# MIDI_Output.net
KiCad netlist of a schematic drawn in EAGLE
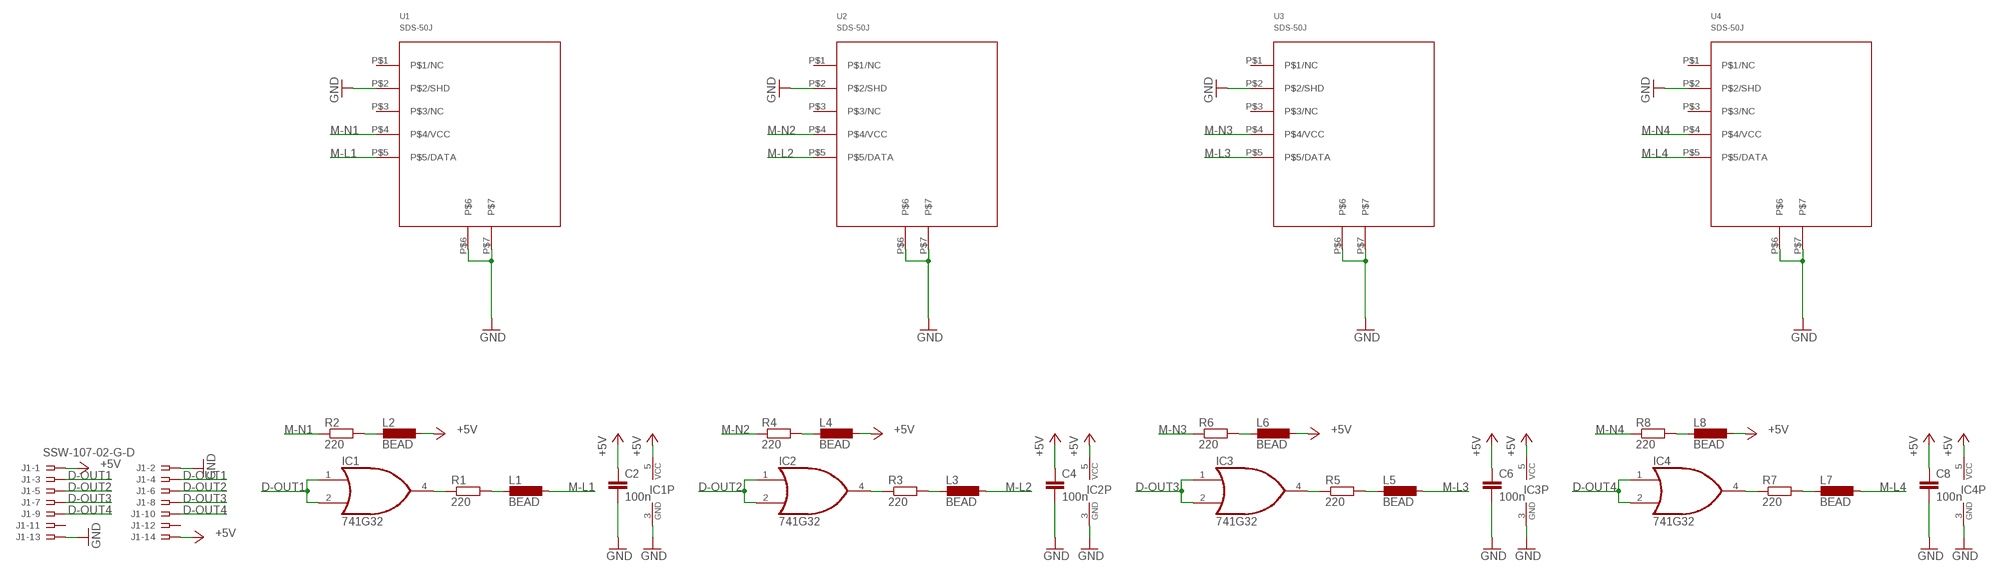
[diagram p0: schematic, sheet 1]

(export (version "E")
  (design (tool "Eeschema 10.0.6"))
  (components
    (comp (ref "C2")
      (value "100n")
      (footprint "eagle-import:C0805")
      (libsource (lib "eagle-import") (part "C-EUC0805"))
    )
    (comp (ref "C4")
      (value "100n")
      (footprint "eagle-import:C0805")
      (libsource (lib "eagle-import") (part "C-EUC0805"))
    )
    (comp (ref "C6")
      (value "100n")
      (footprint "eagle-import:C0805")
      (libsource (lib "eagle-import") (part "C-EUC0805"))
    )
    (comp (ref "C8")
      (value "100n")
      (footprint "eagle-import:C0805")
      (libsource (lib "eagle-import") (part "C-EUC0805"))
    )
    (comp (ref "IC1")
      (value "741G32")
      (footprint "eagle-import:SOT25")
      (fields (field (name "SPICEPREFIX") "J"))
      (libsource (lib "eagle-import") (part "741G32"))
    )
    (comp (ref "IC2")
      (value "741G32")
      (footprint "eagle-import:SOT25")
      (fields (field (name "SPICEPREFIX") "J"))
      (libsource (lib "eagle-import") (part "741G32"))
    )
    (comp (ref "IC3")
      (value "741G32")
      (footprint "eagle-import:SOT25")
      (fields (field (name "SPICEPREFIX") "J"))
      (libsource (lib "eagle-import") (part "741G32"))
    )
    (comp (ref "IC4")
      (value "741G32")
      (footprint "eagle-import:SOT25")
      (fields (field (name "SPICEPREFIX") "J"))
      (libsource (lib "eagle-import") (part "741G32"))
    )
    (comp (ref "J1")
      (value "SSW-107-02-G-D")
      (footprint "eagle-import:SSW-107-02-G-D")
      (fields (field (name "MF") "Samtec Inc."))
      (libsource (lib "eagle-import") (part "SSW-107-02-G-D"))
    )
    (comp (ref "L1")
      (value "BEAD")
      (footprint "eagle-import:L0805")
      (libsource (lib "eagle-import") (part "BEAD"))
    )
    (comp (ref "L2")
      (value "BEAD")
      (footprint "eagle-import:L0805")
      (libsource (lib "eagle-import") (part "BEAD"))
    )
    (comp (ref "L3")
      (value "BEAD")
      (footprint "eagle-import:L0805")
      (libsource (lib "eagle-import") (part "BEAD"))
    )
    (comp (ref "L4")
      (value "BEAD")
      (footprint "eagle-import:L0805")
      (libsource (lib "eagle-import") (part "BEAD"))
    )
    (comp (ref "L5")
      (value "BEAD")
      (footprint "eagle-import:L0805")
      (libsource (lib "eagle-import") (part "BEAD"))
    )
    (comp (ref "L6")
      (value "BEAD")
      (footprint "eagle-import:L0805")
      (libsource (lib "eagle-import") (part "BEAD"))
    )
    (comp (ref "L7")
      (value "BEAD")
      (footprint "eagle-import:L0805")
      (libsource (lib "eagle-import") (part "BEAD"))
    )
    (comp (ref "L8")
      (value "BEAD")
      (footprint "eagle-import:L0805")
      (libsource (lib "eagle-import") (part "BEAD"))
    )
    (comp (ref "R1")
      (value "220")
      (footprint "eagle-import:R0805")
      (libsource (lib "eagle-import") (part "R-EU_R0805"))
    )
    (comp (ref "R2")
      (value "220")
      (footprint "eagle-import:R0805")
      (libsource (lib "eagle-import") (part "R-EU_R0805"))
    )
    (comp (ref "R3")
      (value "220")
      (footprint "eagle-import:R0805")
      (libsource (lib "eagle-import") (part "R-EU_R0805"))
    )
    (comp (ref "R4")
      (value "220")
      (footprint "eagle-import:R0805")
      (libsource (lib "eagle-import") (part "R-EU_R0805"))
    )
    (comp (ref "R5")
      (value "220")
      (footprint "eagle-import:R0805")
      (libsource (lib "eagle-import") (part "R-EU_R0805"))
    )
    (comp (ref "R6")
      (value "220")
      (footprint "eagle-import:R0805")
      (libsource (lib "eagle-import") (part "R-EU_R0805"))
    )
    (comp (ref "R7")
      (value "220")
      (footprint "eagle-import:R0805")
      (libsource (lib "eagle-import") (part "R-EU_R0805"))
    )
    (comp (ref "R8")
      (value "220")
      (footprint "eagle-import:R0805")
      (libsource (lib "eagle-import") (part "R-EU_R0805"))
    )
    (comp (ref "U1")
      (value "SDS-50J")
      (footprint "eagle-import:SDS-50J")
      (libsource (lib "eagle-import") (part "SDS-50J"))
    )
    (comp (ref "U2")
      (value "SDS-50J")
      (footprint "eagle-import:SDS-50J")
      (libsource (lib "eagle-import") (part "SDS-50J"))
    )
    (comp (ref "U3")
      (value "SDS-50J")
      (footprint "eagle-import:SDS-50J")
      (libsource (lib "eagle-import") (part "SDS-50J"))
    )
    (comp (ref "U4")
      (value "SDS-50J")
      (footprint "eagle-import:SDS-50J")
      (libsource (lib "eagle-import") (part "SDS-50J"))
    )
  )
  (nets
    (net (code "1") (name "+5V") (class "Default")
      (node (ref "C2") (pin "1") (pinfunction "1_1") (pintype "passive"))
      (node (ref "C4") (pin "1") (pinfunction "1_1") (pintype "passive"))
      (node (ref "C6") (pin "1") (pinfunction "1_1") (pintype "passive"))
      (node (ref "C8") (pin "1") (pinfunction "1_1") (pintype "passive"))
      (node (ref "IC1") (pin "5") (pinfunction "VCC_5") (pintype "power_in"))
      (node (ref "IC2") (pin "5") (pinfunction "VCC_5") (pintype "power_in"))
      (node (ref "IC3") (pin "5") (pinfunction "VCC_5") (pintype "power_in"))
      (node (ref "IC4") (pin "5") (pinfunction "VCC_5") (pintype "power_in"))
      (node (ref "J1") (pin "1") (pinfunction "1_1") (pintype "passive"))
      (node (ref "J1") (pin "14") (pinfunction "1_14") (pintype "passive"))
      (node (ref "L2") (pin "2") (pinfunction "2_2") (pintype "passive"))
      (node (ref "L4") (pin "2") (pinfunction "2_2") (pintype "passive"))
      (node (ref "L6") (pin "2") (pinfunction "2_2") (pintype "passive"))
      (node (ref "L8") (pin "2") (pinfunction "2_2") (pintype "passive"))
    )
    (net (code "2") (name "/D-OUT1") (class "Default")
      (node (ref "IC1") (pin "1") (pinfunction "I0_1") (pintype "input"))
      (node (ref "IC1") (pin "2") (pinfunction "I1_2") (pintype "input"))
      (node (ref "J1") (pin "3") (pinfunction "1_3") (pintype "passive"))
      (node (ref "J1") (pin "4") (pinfunction "1_4") (pintype "passive"))
    )
    (net (code "3") (name "/D-OUT2") (class "Default")
      (node (ref "IC2") (pin "1") (pinfunction "I0_1") (pintype "input"))
      (node (ref "IC2") (pin "2") (pinfunction "I1_2") (pintype "input"))
      (node (ref "J1") (pin "5") (pinfunction "1_5") (pintype "passive"))
      (node (ref "J1") (pin "6") (pinfunction "1_6") (pintype "passive"))
    )
    (net (code "4") (name "/D-OUT3") (class "Default")
      (node (ref "IC3") (pin "1") (pinfunction "I0_1") (pintype "input"))
      (node (ref "IC3") (pin "2") (pinfunction "I1_2") (pintype "input"))
      (node (ref "J1") (pin "7") (pinfunction "1_7") (pintype "passive"))
      (node (ref "J1") (pin "8") (pinfunction "1_8") (pintype "passive"))
    )
    (net (code "5") (name "/D-OUT4") (class "Default")
      (node (ref "IC4") (pin "1") (pinfunction "I0_1") (pintype "input"))
      (node (ref "IC4") (pin "2") (pinfunction "I1_2") (pintype "input"))
      (node (ref "J1") (pin "10") (pinfunction "1_10") (pintype "passive"))
      (node (ref "J1") (pin "9") (pinfunction "1_9") (pintype "passive"))
    )
    (net (code "6") (name "/M-L1") (class "Default")
      (node (ref "L1") (pin "2") (pinfunction "2_2") (pintype "passive"))
      (node (ref "U1") (pin "P$5") (pinfunction "P$5/DATA_P$5") (pintype "bidirectional"))
    )
    (net (code "7") (name "/M-L2") (class "Default")
      (node (ref "L3") (pin "2") (pinfunction "2_2") (pintype "passive"))
      (node (ref "U2") (pin "P$5") (pinfunction "P$5/DATA_P$5") (pintype "bidirectional"))
    )
    (net (code "8") (name "/M-L3") (class "Default")
      (node (ref "L5") (pin "2") (pinfunction "2_2") (pintype "passive"))
      (node (ref "U3") (pin "P$5") (pinfunction "P$5/DATA_P$5") (pintype "bidirectional"))
    )
    (net (code "9") (name "/M-L4") (class "Default")
      (node (ref "L7") (pin "2") (pinfunction "2_2") (pintype "passive"))
      (node (ref "U4") (pin "P$5") (pinfunction "P$5/DATA_P$5") (pintype "bidirectional"))
    )
    (net (code "10") (name "/M-N1") (class "Default")
      (node (ref "R2") (pin "1") (pinfunction "1_1") (pintype "passive"))
      (node (ref "U1") (pin "P$4") (pinfunction "P$4/VCC_P$4") (pintype "bidirectional"))
    )
    (net (code "11") (name "/M-N2") (class "Default")
      (node (ref "R4") (pin "1") (pinfunction "1_1") (pintype "passive"))
      (node (ref "U2") (pin "P$4") (pinfunction "P$4/VCC_P$4") (pintype "bidirectional"))
    )
    (net (code "12") (name "/M-N3") (class "Default")
      (node (ref "R6") (pin "1") (pinfunction "1_1") (pintype "passive"))
      (node (ref "U3") (pin "P$4") (pinfunction "P$4/VCC_P$4") (pintype "bidirectional"))
    )
    (net (code "13") (name "/M-N4") (class "Default")
      (node (ref "R8") (pin "1") (pinfunction "1_1") (pintype "passive"))
      (node (ref "U4") (pin "P$4") (pinfunction "P$4/VCC_P$4") (pintype "bidirectional"))
    )
    (net (code "14") (name "GND") (class "Default")
      (node (ref "C2") (pin "2") (pinfunction "2_2") (pintype "passive"))
      (node (ref "C4") (pin "2") (pinfunction "2_2") (pintype "passive"))
      (node (ref "C6") (pin "2") (pinfunction "2_2") (pintype "passive"))
      (node (ref "C8") (pin "2") (pinfunction "2_2") (pintype "passive"))
      (node (ref "IC1") (pin "3") (pinfunction "GND_3") (pintype "power_in"))
      (node (ref "IC2") (pin "3") (pinfunction "GND_3") (pintype "power_in"))
      (node (ref "IC3") (pin "3") (pinfunction "GND_3") (pintype "power_in"))
      (node (ref "IC4") (pin "3") (pinfunction "GND_3") (pintype "power_in"))
      (node (ref "J1") (pin "13") (pinfunction "1_13") (pintype "passive"))
      (node (ref "J1") (pin "2") (pinfunction "1_2") (pintype "passive"))
      (node (ref "U1") (pin "P$2") (pinfunction "P$2/SHD_P$2") (pintype "bidirectional"))
      (node (ref "U1") (pin "P$6") (pinfunction "P$6_P$6") (pintype "bidirectional"))
      (node (ref "U1") (pin "P$7") (pinfunction "P$7_P$7") (pintype "bidirectional"))
      (node (ref "U2") (pin "P$2") (pinfunction "P$2/SHD_P$2") (pintype "bidirectional"))
      (node (ref "U2") (pin "P$6") (pinfunction "P$6_P$6") (pintype "bidirectional"))
      (node (ref "U2") (pin "P$7") (pinfunction "P$7_P$7") (pintype "bidirectional"))
      (node (ref "U3") (pin "P$2") (pinfunction "P$2/SHD_P$2") (pintype "bidirectional"))
      (node (ref "U3") (pin "P$6") (pinfunction "P$6_P$6") (pintype "bidirectional"))
      (node (ref "U3") (pin "P$7") (pinfunction "P$7_P$7") (pintype "bidirectional"))
      (node (ref "U4") (pin "P$2") (pinfunction "P$2/SHD_P$2") (pintype "bidirectional"))
      (node (ref "U4") (pin "P$6") (pinfunction "P$6_P$6") (pintype "bidirectional"))
      (node (ref "U4") (pin "P$7") (pinfunction "P$7_P$7") (pintype "bidirectional"))
    )
    (net (code "15") (name "Net-(IC1A-O)") (class "Default")
      (node (ref "IC1") (pin "4") (pinfunction "O_4") (pintype "output"))
      (node (ref "R1") (pin "1") (pinfunction "1_1") (pintype "passive"))
    )
    (net (code "16") (name "Net-(IC2A-O)") (class "Default")
      (node (ref "IC2") (pin "4") (pinfunction "O_4") (pintype "output"))
      (node (ref "R3") (pin "1") (pinfunction "1_1") (pintype "passive"))
    )
    (net (code "17") (name "Net-(IC3A-O)") (class "Default")
      (node (ref "IC3") (pin "4") (pinfunction "O_4") (pintype "output"))
      (node (ref "R5") (pin "1") (pinfunction "1_1") (pintype "passive"))
    )
    (net (code "18") (name "Net-(IC4A-O)") (class "Default")
      (node (ref "IC4") (pin "4") (pinfunction "O_4") (pintype "output"))
      (node (ref "R7") (pin "1") (pinfunction "1_1") (pintype "passive"))
    )
    (net (code "19") (name "Net-(L1-Pad1)") (class "Default")
      (node (ref "L1") (pin "1") (pinfunction "1_1") (pintype "passive"))
      (node (ref "R1") (pin "2") (pinfunction "2_2") (pintype "passive"))
    )
    (net (code "20") (name "Net-(L2-Pad1)") (class "Default")
      (node (ref "L2") (pin "1") (pinfunction "1_1") (pintype "passive"))
      (node (ref "R2") (pin "2") (pinfunction "2_2") (pintype "passive"))
    )
    (net (code "21") (name "Net-(L3-Pad1)") (class "Default")
      (node (ref "L3") (pin "1") (pinfunction "1_1") (pintype "passive"))
      (node (ref "R3") (pin "2") (pinfunction "2_2") (pintype "passive"))
    )
    (net (code "22") (name "Net-(L4-Pad1)") (class "Default")
      (node (ref "L4") (pin "1") (pinfunction "1_1") (pintype "passive"))
      (node (ref "R4") (pin "2") (pinfunction "2_2") (pintype "passive"))
    )
    (net (code "23") (name "Net-(L5-Pad1)") (class "Default")
      (node (ref "L5") (pin "1") (pinfunction "1_1") (pintype "passive"))
      (node (ref "R5") (pin "2") (pinfunction "2_2") (pintype "passive"))
    )
    (net (code "24") (name "Net-(L6-Pad1)") (class "Default")
      (node (ref "L6") (pin "1") (pinfunction "1_1") (pintype "passive"))
      (node (ref "R6") (pin "2") (pinfunction "2_2") (pintype "passive"))
    )
    (net (code "25") (name "Net-(L7-Pad1)") (class "Default")
      (node (ref "L7") (pin "1") (pinfunction "1_1") (pintype "passive"))
      (node (ref "R7") (pin "2") (pinfunction "2_2") (pintype "passive"))
    )
    (net (code "26") (name "Net-(L8-Pad1)") (class "Default")
      (node (ref "L8") (pin "1") (pinfunction "1_1") (pintype "passive"))
      (node (ref "R8") (pin "2") (pinfunction "2_2") (pintype "passive"))
    )
    (net (code "27") (name "unconnected-(J1C-1-Pad11)") (class "Default")
      (node (ref "J1") (pin "11") (pinfunction "1_11") (pintype "passive"))
    )
    (net (code "28") (name "unconnected-(J1D-1-Pad12)") (class "Default")
      (node (ref "J1") (pin "12") (pinfunction "1_12") (pintype "passive"))
    )
    (net (code "29") (name "unconnected-(U1-P$1{slash}NC-PadP$1)") (class "Default")
      (node (ref "U1") (pin "P$1") (pinfunction "P$1/NC_P$1") (pintype "bidirectional"))
    )
    (net (code "30") (name "unconnected-(U1-P$3{slash}NC-PadP$3)") (class "Default")
      (node (ref "U1") (pin "P$3") (pinfunction "P$3/NC_P$3") (pintype "bidirectional"))
    )
    (net (code "31") (name "unconnected-(U2-P$1{slash}NC-PadP$1)") (class "Default")
      (node (ref "U2") (pin "P$1") (pinfunction "P$1/NC_P$1") (pintype "bidirectional"))
    )
    (net (code "32") (name "unconnected-(U2-P$3{slash}NC-PadP$3)") (class "Default")
      (node (ref "U2") (pin "P$3") (pinfunction "P$3/NC_P$3") (pintype "bidirectional"))
    )
    (net (code "33") (name "unconnected-(U3-P$1{slash}NC-PadP$1)") (class "Default")
      (node (ref "U3") (pin "P$1") (pinfunction "P$1/NC_P$1") (pintype "bidirectional"))
    )
    (net (code "34") (name "unconnected-(U3-P$3{slash}NC-PadP$3)") (class "Default")
      (node (ref "U3") (pin "P$3") (pinfunction "P$3/NC_P$3") (pintype "bidirectional"))
    )
    (net (code "35") (name "unconnected-(U4-P$1{slash}NC-PadP$1)") (class "Default")
      (node (ref "U4") (pin "P$1") (pinfunction "P$1/NC_P$1") (pintype "bidirectional"))
    )
    (net (code "36") (name "unconnected-(U4-P$3{slash}NC-PadP$3)") (class "Default")
      (node (ref "U4") (pin "P$3") (pinfunction "P$3/NC_P$3") (pintype "bidirectional"))
    )
  )
)
